# MCU.net
KiCad netlist of a schematic drawn in Altium Designer
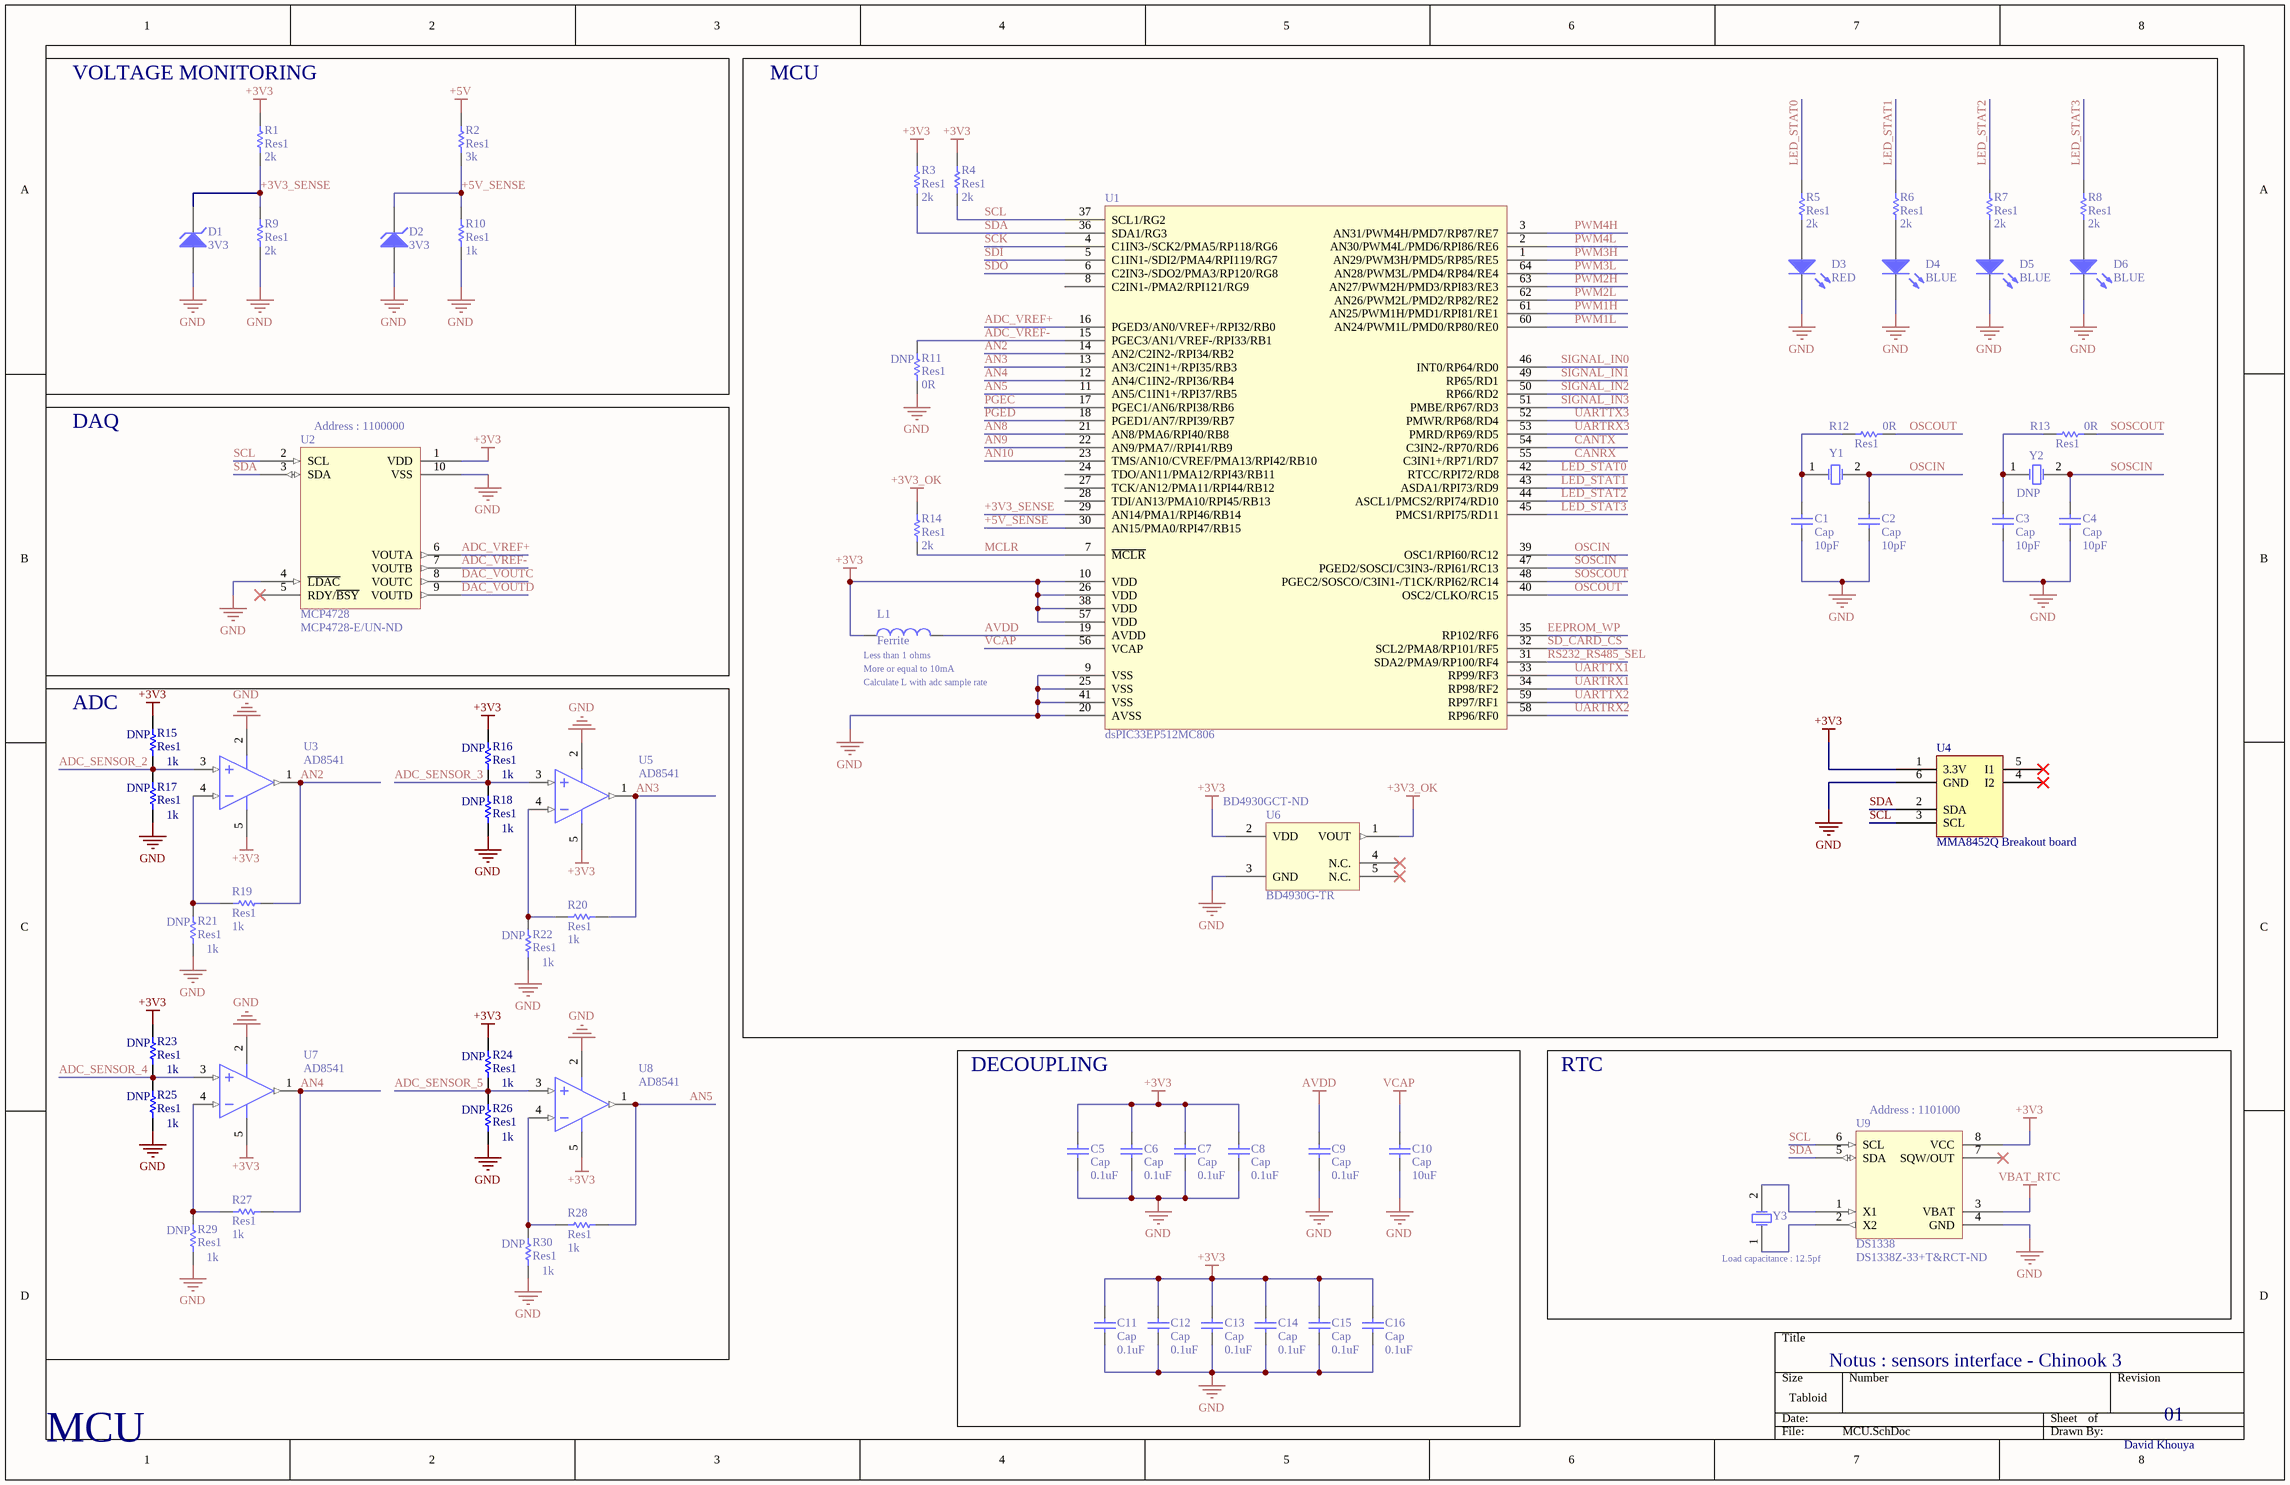
[diagram p0: MCU.SchDoc]

(export (version "E")
  (design (tool "Eeschema 10.0.6"))
  (components
    (comp (ref "C1")
      (value "Cap")
      (footprint "RESC2012N")
      (description "Capacitor")
      (fields (field (name "ALTIUM_VALUE") "10pF") (field (name "PUBLISHER") "Altium Limited"))
      (libsource (lib "Miscellaneous Devices") (part "Cap"))
    )
    (comp (ref "C2")
      (value "Cap")
      (footprint "RESC2012N")
      (description "Capacitor")
      (fields (field (name "ALTIUM_VALUE") "10pF") (field (name "PUBLISHER") "Altium Limited"))
      (libsource (lib "Miscellaneous Devices") (part "Cap"))
    )
    (comp (ref "C3")
      (value "Cap")
      (footprint "RESC2012N")
      (description "Capacitor")
      (fields (field (name "ALTIUM_VALUE") "10pF") (field (name "PUBLISHER") "Altium Limited"))
      (libsource (lib "Miscellaneous Devices") (part "Cap"))
    )
    (comp (ref "C4")
      (value "Cap")
      (footprint "RESC2012N")
      (description "Capacitor")
      (fields (field (name "ALTIUM_VALUE") "10pF") (field (name "PUBLISHER") "Altium Limited"))
      (libsource (lib "Miscellaneous Devices") (part "Cap"))
    )
    (comp (ref "C5")
      (value "Cap")
      (footprint "RESC2012N")
      (description "Capacitor")
      (fields (field (name "ALTIUM_VALUE") "0.1uF") (field (name "PUBLISHER") "Altium Limited"))
      (libsource (lib "Miscellaneous Devices") (part "Cap"))
    )
    (comp (ref "C6")
      (value "Cap")
      (footprint "RESC2012N")
      (description "Capacitor")
      (fields (field (name "ALTIUM_VALUE") "0.1uF") (field (name "PUBLISHER") "Altium Limited"))
      (libsource (lib "Miscellaneous Devices") (part "Cap"))
    )
    (comp (ref "C7")
      (value "Cap")
      (footprint "RESC2012N")
      (description "Capacitor")
      (fields (field (name "ALTIUM_VALUE") "0.1uF") (field (name "PUBLISHER") "Altium Limited"))
      (libsource (lib "Miscellaneous Devices") (part "Cap"))
    )
    (comp (ref "C8")
      (value "Cap")
      (footprint "RESC2012N")
      (description "Capacitor")
      (fields (field (name "ALTIUM_VALUE") "0.1uF") (field (name "PUBLISHER") "Altium Limited"))
      (libsource (lib "Miscellaneous Devices") (part "Cap"))
    )
    (comp (ref "C9")
      (value "Cap")
      (footprint "RESC2012N")
      (description "Capacitor")
      (fields (field (name "ALTIUM_VALUE") "0.1uF") (field (name "PUBLISHER") "Altium Limited"))
      (libsource (lib "Miscellaneous Devices") (part "Cap"))
    )
    (comp (ref "C10")
      (value "Cap")
      (footprint "RESC2012N")
      (description "Capacitor")
      (fields (field (name "ALTIUM_VALUE") "10uF") (field (name "PUBLISHER") "Altium Limited"))
      (libsource (lib "Miscellaneous Devices") (part "Cap"))
    )
    (comp (ref "C11")
      (value "Cap")
      (footprint "RESC2012N")
      (description "Capacitor")
      (fields (field (name "ALTIUM_VALUE") "0.1uF") (field (name "PUBLISHER") "Altium Limited"))
      (libsource (lib "Miscellaneous Devices") (part "Cap"))
    )
    (comp (ref "C12")
      (value "Cap")
      (footprint "RESC2012N")
      (description "Capacitor")
      (fields (field (name "ALTIUM_VALUE") "0.1uF") (field (name "PUBLISHER") "Altium Limited"))
      (libsource (lib "Miscellaneous Devices") (part "Cap"))
    )
    (comp (ref "C13")
      (value "Cap")
      (footprint "RESC2012N")
      (description "Capacitor")
      (fields (field (name "ALTIUM_VALUE") "0.1uF") (field (name "PUBLISHER") "Altium Limited"))
      (libsource (lib "Miscellaneous Devices") (part "Cap"))
    )
    (comp (ref "C14")
      (value "Cap")
      (footprint "RESC2012N")
      (description "Capacitor")
      (fields (field (name "ALTIUM_VALUE") "0.1uF") (field (name "PUBLISHER") "Altium Limited"))
      (libsource (lib "Miscellaneous Devices") (part "Cap"))
    )
    (comp (ref "C15")
      (value "Cap")
      (footprint "RESC2012N")
      (description "Capacitor")
      (fields (field (name "ALTIUM_VALUE") "0.1uF") (field (name "PUBLISHER") "Altium Limited"))
      (libsource (lib "Miscellaneous Devices") (part "Cap"))
    )
    (comp (ref "C16")
      (value "Cap")
      (footprint "RESC2012N")
      (description "Capacitor")
      (fields (field (name "ALTIUM_VALUE") "0.1uF") (field (name "PUBLISHER") "Altium Limited"))
      (libsource (lib "Miscellaneous Devices") (part "Cap"))
    )
    (comp (ref "D1")
      (value "3V3")
      (footprint "SOT23-3M")
      (description "Zener Diode")
      (fields (field (name "PUBLISHER") "Altium Limited"))
      (libsource (lib "Miscellaneous Devices") (part "D Zener"))
    )
    (comp (ref "D2")
      (value "3V3")
      (footprint "SOT23-3M")
      (description "Zener Diode")
      (fields (field (name "PUBLISHER") "Altium Limited"))
      (libsource (lib "Miscellaneous Devices") (part "D Zener"))
    )
    (comp (ref "D3")
      (value "RED")
      (footprint "0805_Diode")
      (description "Typical INFRARED GaAs LED")
      (fields (field (name "PUBLISHER") "Altium Limited"))
      (libsource (lib "Miscellaneous Devices") (part "LED0"))
    )
    (comp (ref "D4")
      (value "BLUE")
      (footprint "0805_Diode")
      (description "Typical INFRARED GaAs LED")
      (fields (field (name "PUBLISHER") "Altium Limited"))
      (libsource (lib "Miscellaneous Devices") (part "LED0"))
    )
    (comp (ref "D5")
      (value "BLUE")
      (footprint "0805_Diode")
      (description "Typical INFRARED GaAs LED")
      (fields (field (name "PUBLISHER") "Altium Limited"))
      (libsource (lib "Miscellaneous Devices") (part "LED0"))
    )
    (comp (ref "D6")
      (value "BLUE")
      (footprint "0805_Diode")
      (description "Typical INFRARED GaAs LED")
      (fields (field (name "PUBLISHER") "Altium Limited"))
      (libsource (lib "Miscellaneous Devices") (part "LED0"))
    )
    (comp (ref "L1")
      (value "Ferrite")
      (footprint "RESC2012N")
      (description "Inductor")
      (fields (field (name "PUBLISHER") "Altium Limited"))
      (libsource (lib "Miscellaneous Devices") (part "Inductor"))
    )
    (comp (ref "R1")
      (value "Res1")
      (footprint "RESC2012N")
      (description "Resistor")
      (fields (field (name "ALTIUM_VALUE") "2k") (field (name "PUBLISHER") "Altium Limited"))
      (libsource (lib "Miscellaneous Devices") (part "Res1"))
    )
    (comp (ref "R2")
      (value "Res1")
      (footprint "RESC2012N")
      (description "Resistor")
      (fields (field (name "ALTIUM_VALUE") "3k") (field (name "PUBLISHER") "Altium Limited"))
      (libsource (lib "Miscellaneous Devices") (part "Res1"))
    )
    (comp (ref "R3")
      (value "Res1")
      (footprint "RESC2012N")
      (description "Resistor")
      (fields (field (name "ALTIUM_VALUE") "2k") (field (name "PUBLISHER") "Altium Limited"))
      (libsource (lib "Miscellaneous Devices") (part "Res1"))
    )
    (comp (ref "R4")
      (value "Res1")
      (footprint "RESC2012N")
      (description "Resistor")
      (fields (field (name "ALTIUM_VALUE") "2k") (field (name "PUBLISHER") "Altium Limited"))
      (libsource (lib "Miscellaneous Devices") (part "Res1"))
    )
    (comp (ref "R5")
      (value "Res1")
      (footprint "RESC2012N")
      (description "Resistor")
      (fields (field (name "ALTIUM_VALUE") "2k") (field (name "PUBLISHER") "Altium Limited"))
      (libsource (lib "Miscellaneous Devices") (part "Res1"))
    )
    (comp (ref "R6")
      (value "Res1")
      (footprint "RESC2012N")
      (description "Resistor")
      (fields (field (name "ALTIUM_VALUE") "2k") (field (name "PUBLISHER") "Altium Limited"))
      (libsource (lib "Miscellaneous Devices") (part "Res1"))
    )
    (comp (ref "R7")
      (value "Res1")
      (footprint "RESC2012N")
      (description "Resistor")
      (fields (field (name "ALTIUM_VALUE") "2k") (field (name "PUBLISHER") "Altium Limited"))
      (libsource (lib "Miscellaneous Devices") (part "Res1"))
    )
    (comp (ref "R8")
      (value "Res1")
      (footprint "RESC2012N")
      (description "Resistor")
      (fields (field (name "ALTIUM_VALUE") "2k") (field (name "PUBLISHER") "Altium Limited"))
      (libsource (lib "Miscellaneous Devices") (part "Res1"))
    )
    (comp (ref "R9")
      (value "Res1")
      (footprint "RESC2012N")
      (description "Resistor")
      (fields (field (name "ALTIUM_VALUE") "2k") (field (name "PUBLISHER") "Altium Limited"))
      (libsource (lib "Miscellaneous Devices") (part "Res1"))
    )
    (comp (ref "R10")
      (value "Res1")
      (footprint "RESC2012N")
      (description "Resistor")
      (fields (field (name "ALTIUM_VALUE") "1k") (field (name "PUBLISHER") "Altium Limited"))
      (libsource (lib "Miscellaneous Devices") (part "Res1"))
    )
    (comp (ref "R11")
      (value "Res1")
      (footprint "RESC2012N")
      (description "Resistor")
      (fields
        (field (name "ALTIUM_VALUE") "0R")
        (field (name "DNP") "DNP")
        (field (name "PUBLISHER") "Altium Limited")
      )
      (libsource (lib "Miscellaneous Devices") (part "Res1"))
    )
    (comp (ref "R12")
      (value "Res1")
      (footprint "RESC2012N")
      (description "Resistor")
      (fields (field (name "ALTIUM_VALUE") "0R") (field (name "PUBLISHER") "Altium Limited"))
      (libsource (lib "Miscellaneous Devices") (part "Res1"))
    )
    (comp (ref "R13")
      (value "Res1")
      (footprint "RESC2012N")
      (description "Resistor")
      (fields (field (name "ALTIUM_VALUE") "0R") (field (name "PUBLISHER") "Altium Limited"))
      (libsource (lib "Miscellaneous Devices") (part "Res1"))
    )
    (comp (ref "R14")
      (value "Res1")
      (footprint "RESC2012N")
      (description "Resistor")
      (fields (field (name "ALTIUM_VALUE") "2k") (field (name "PUBLISHER") "Altium Limited"))
      (libsource (lib "Miscellaneous Devices") (part "Res1"))
    )
    (comp (ref "R15")
      (value "Res1")
      (footprint "RESC2012N")
      (description "Resistor")
      (fields
        (field (name "ALTIUM_VALUE") "1k")
        (field (name "DNP") "DNP")
        (field (name "PUBLISHER") "Altium Limited")
      )
      (libsource (lib "Miscellaneous Devices") (part "Res1"))
    )
    (comp (ref "R16")
      (value "Res1")
      (footprint "RESC2012N")
      (description "Resistor")
      (fields
        (field (name "ALTIUM_VALUE") "1k")
        (field (name "DNP") "DNP")
        (field (name "PUBLISHER") "Altium Limited")
      )
      (libsource (lib "Miscellaneous Devices") (part "Res1"))
    )
    (comp (ref "R17")
      (value "Res1")
      (footprint "RESC2012N")
      (description "Resistor")
      (fields
        (field (name "ALTIUM_VALUE") "1k")
        (field (name "DNP") "DNP")
        (field (name "PUBLISHER") "Altium Limited")
      )
      (libsource (lib "Miscellaneous Devices") (part "Res1"))
    )
    (comp (ref "R18")
      (value "Res1")
      (footprint "RESC2012N")
      (description "Resistor")
      (fields
        (field (name "ALTIUM_VALUE") "1k")
        (field (name "DNP") "DNP")
        (field (name "PUBLISHER") "Altium Limited")
      )
      (libsource (lib "Miscellaneous Devices") (part "Res1"))
    )
    (comp (ref "R19")
      (value "Res1")
      (footprint "RESC2012N")
      (description "Resistor")
      (fields (field (name "ALTIUM_VALUE") "1k") (field (name "PUBLISHER") "Altium Limited"))
      (libsource (lib "Miscellaneous Devices") (part "Res1"))
    )
    (comp (ref "R20")
      (value "Res1")
      (footprint "RESC2012N")
      (description "Resistor")
      (fields (field (name "ALTIUM_VALUE") "1k") (field (name "PUBLISHER") "Altium Limited"))
      (libsource (lib "Miscellaneous Devices") (part "Res1"))
    )
    (comp (ref "R21")
      (value "Res1")
      (footprint "RESC2012N")
      (description "Resistor")
      (fields
        (field (name "ALTIUM_VALUE") "1k")
        (field (name "DNP") "DNP")
        (field (name "PUBLISHER") "Altium Limited")
      )
      (libsource (lib "Miscellaneous Devices") (part "Res1"))
    )
    (comp (ref "R22")
      (value "Res1")
      (footprint "RESC2012N")
      (description "Resistor")
      (fields
        (field (name "ALTIUM_VALUE") "1k")
        (field (name "DNP") "DNP")
        (field (name "PUBLISHER") "Altium Limited")
      )
      (libsource (lib "Miscellaneous Devices") (part "Res1"))
    )
    (comp (ref "R23")
      (value "Res1")
      (footprint "RESC2012N")
      (description "Resistor")
      (fields
        (field (name "ALTIUM_VALUE") "1k")
        (field (name "DNP") "DNP")
        (field (name "PUBLISHER") "Altium Limited")
      )
      (libsource (lib "Miscellaneous Devices") (part "Res1"))
    )
    (comp (ref "R24")
      (value "Res1")
      (footprint "RESC2012N")
      (description "Resistor")
      (fields
        (field (name "ALTIUM_VALUE") "1k")
        (field (name "DNP") "DNP")
        (field (name "PUBLISHER") "Altium Limited")
      )
      (libsource (lib "Miscellaneous Devices") (part "Res1"))
    )
    (comp (ref "R25")
      (value "Res1")
      (footprint "RESC2012N")
      (description "Resistor")
      (fields
        (field (name "ALTIUM_VALUE") "1k")
        (field (name "DNP") "DNP")
        (field (name "PUBLISHER") "Altium Limited")
      )
      (libsource (lib "Miscellaneous Devices") (part "Res1"))
    )
    (comp (ref "R26")
      (value "Res1")
      (footprint "RESC2012N")
      (description "Resistor")
      (fields
        (field (name "ALTIUM_VALUE") "1k")
        (field (name "DNP") "DNP")
        (field (name "PUBLISHER") "Altium Limited")
      )
      (libsource (lib "Miscellaneous Devices") (part "Res1"))
    )
    (comp (ref "R27")
      (value "Res1")
      (footprint "RESC2012N")
      (description "Resistor")
      (fields (field (name "ALTIUM_VALUE") "1k") (field (name "PUBLISHER") "Altium Limited"))
      (libsource (lib "Miscellaneous Devices") (part "Res1"))
    )
    (comp (ref "R28")
      (value "Res1")
      (footprint "RESC2012N")
      (description "Resistor")
      (fields (field (name "ALTIUM_VALUE") "1k") (field (name "PUBLISHER") "Altium Limited"))
      (libsource (lib "Miscellaneous Devices") (part "Res1"))
    )
    (comp (ref "R29")
      (value "Res1")
      (footprint "RESC2012N")
      (description "Resistor")
      (fields
        (field (name "ALTIUM_VALUE") "1k")
        (field (name "DNP") "DNP")
        (field (name "PUBLISHER") "Altium Limited")
      )
      (libsource (lib "Miscellaneous Devices") (part "Res1"))
    )
    (comp (ref "R30")
      (value "Res1")
      (footprint "RESC2012N")
      (description "Resistor")
      (fields
        (field (name "ALTIUM_VALUE") "1k")
        (field (name "DNP") "DNP")
        (field (name "PUBLISHER") "Altium Limited")
      )
      (libsource (lib "Miscellaneous Devices") (part "Res1"))
    )
    (comp (ref "U1")
      (value "dsPIC33EP512MC806")
      (footprint "TQFP-PT64_M")
      (description "16 bits microcontroller with Digital signal controller")
      (libsource (lib "dkhouya") (part "dsPIC33EP512MC806"))
    )
    (comp (ref "U2")
      (value "MCP4728")
      (description "12-Bit, Quad Digital-to-Analog Converter with EEPROM Memory")
      (fields (field (name "SUPPLIER PART NUMBER 1") "MCP4728-E/UN-ND"))
      (libsource (lib "dkhouya") (part "MCP4728"))
    )
    (comp (ref "U3")
      (value "AD8541")
      (footprint "RT-5")
      (description "CMOS Rail-to-Rail General-Purpose Amplifiers")
      (libsource (lib "dkhouya") (part "AD8541"))
    )
    (comp (ref "U4")
      (value "MMA8452Q Breakout board")
      (footprint "MMA8452Q Breakout board")
      (description "Triple axis accelerometer breakout board")
      (libsource (lib "dkhouya") (part "MMA8452Q Breakout board"))
    )
    (comp (ref "U5")
      (value "AD8541")
      (footprint "RT-5")
      (description "CMOS Rail-to-Rail General-Purpose Amplifiers")
      (libsource (lib "dkhouya") (part "AD8541"))
    )
    (comp (ref "U6")
      (value "BD4930G-TR")
      (footprint "SSOP5")
      (description "5V Voltage supervisor")
      (fields (field (name "SUPPLIER PART NUMBER 1") "BD4930GCT-ND"))
      (libsource (lib "dkhouya") (part "BD4950G-TR"))
    )
    (comp (ref "U7")
      (value "AD8541")
      (footprint "RT-5")
      (description "CMOS Rail-to-Rail General-Purpose Amplifiers")
      (libsource (lib "dkhouya") (part "AD8541"))
    )
    (comp (ref "U8")
      (value "AD8541")
      (footprint "RT-5")
      (description "CMOS Rail-to-Rail General-Purpose Amplifiers")
      (libsource (lib "dkhouya") (part "AD8541"))
    )
    (comp (ref "U9")
      (value "DS1338")
      (footprint "8SOIC-1")
      (description "I2C RTC with 56-Byte NV RAM")
      (fields (field (name "SUPPLIER PART NUMBER 1") "DS1338Z-33+T&RCT-ND"))
      (libsource (lib "dkhouya") (part "DS1338"))
    )
    (comp (ref "Y1")
      (value "~")
      (footprint "HC49/4H_SMX")
      (description "Crystal Oscillator")
      (fields (field (name "PUBLISHER") "Altium Limited"))
      (libsource (lib "Miscellaneous Devices") (part "XTAL"))
    )
    (comp (ref "Y2")
      (value "~")
      (footprint "HC49/4H_SMX")
      (description "Crystal Oscillator")
      (fields (field (name "DNP") "DNP") (field (name "PUBLISHER") "Altium Limited"))
      (libsource (lib "Miscellaneous Devices") (part "XTAL"))
    )
    (comp (ref "Y3")
      (value "~")
      (footprint "crystalcustom")
      (description "Crystal Oscillator")
      (fields (field (name "PUBLISHER") "Altium Limited"))
      (libsource (lib "Miscellaneous Devices") (part "XTAL"))
    )
  )
  (nets
    (net (code "1") (name "+3V3") (class "Default")
      (node (ref "C11") (pin "2") (pinfunction "2_2") (pintype "passive"))
      (node (ref "C12") (pin "2") (pinfunction "2_2") (pintype "passive"))
      (node (ref "C13") (pin "2") (pinfunction "2_2") (pintype "passive"))
      (node (ref "C14") (pin "2") (pinfunction "2_2") (pintype "passive"))
      (node (ref "C15") (pin "2") (pinfunction "2_2") (pintype "passive"))
      (node (ref "C16") (pin "2") (pinfunction "2_2") (pintype "passive"))
      (node (ref "C5") (pin "2") (pinfunction "2_2") (pintype "passive"))
      (node (ref "C6") (pin "2") (pinfunction "2_2") (pintype "passive"))
      (node (ref "C7") (pin "2") (pinfunction "2_2") (pintype "passive"))
      (node (ref "C8") (pin "2") (pinfunction "2_2") (pintype "passive"))
      (node (ref "L1") (pin "1") (pinfunction "1_1") (pintype "passive"))
      (node (ref "R1") (pin "1") (pinfunction "1_1") (pintype "passive"))
      (node (ref "R15") (pin "1") (pinfunction "1_1") (pintype "passive"))
      (node (ref "R16") (pin "1") (pinfunction "1_1") (pintype "passive"))
      (node (ref "R23") (pin "1") (pinfunction "1_1") (pintype "passive"))
      (node (ref "R24") (pin "1") (pinfunction "1_1") (pintype "passive"))
      (node (ref "R3") (pin "1") (pinfunction "1_1") (pintype "passive"))
      (node (ref "R4") (pin "1") (pinfunction "1_1") (pintype "passive"))
      (node (ref "U1") (pin "10") (pinfunction "VDD_10") (pintype "passive"))
      (node (ref "U1") (pin "26") (pinfunction "VDD_26") (pintype "passive"))
      (node (ref "U1") (pin "38") (pinfunction "VDD_38") (pintype "passive"))
      (node (ref "U1") (pin "57") (pinfunction "VDD_57") (pintype "passive"))
      (node (ref "U2") (pin "1") (pinfunction "VDD_1") (pintype "power_in"))
      (node (ref "U3") (pin "5") (pinfunction "V+_5") (pintype "power_in"))
      (node (ref "U4") (pin "1") (pinfunction "3.3V_1") (pintype "passive"))
      (node (ref "U5") (pin "5") (pinfunction "V+_5") (pintype "power_in"))
      (node (ref "U6") (pin "2") (pinfunction "VDD_2") (pintype "power_in"))
      (node (ref "U7") (pin "5") (pinfunction "V+_5") (pintype "power_in"))
      (node (ref "U8") (pin "5") (pinfunction "V+_5") (pintype "power_in"))
      (node (ref "U9") (pin "8") (pinfunction "VCC_8") (pintype "power_in"))
    )
    (net (code "2") (name "+3V3_OK") (class "Default")
      (node (ref "R14") (pin "1") (pinfunction "1_1") (pintype "passive"))
      (node (ref "U6") (pin "1") (pinfunction "VOUT_1") (pintype "output"))
    )
    (net (code "3") (name "+5V") (class "Default")
      (node (ref "R2") (pin "1") (pinfunction "1_1") (pintype "passive"))
    )
    (net (code "4") (name "/+3V3_SENSE") (class "Default")
      (node (ref "D1") (pin "2") (pinfunction "K_2") (pintype "passive"))
      (node (ref "R1") (pin "2") (pinfunction "2_2") (pintype "passive"))
      (node (ref "R9") (pin "1") (pinfunction "1_1") (pintype "passive"))
      (node (ref "U1") (pin "29") (pinfunction "AN14/PMA1/RPI46/RB14_29") (pintype "passive"))
    )
    (net (code "5") (name "/+5V_SENSE") (class "Default")
      (node (ref "D2") (pin "2") (pinfunction "K_2") (pintype "passive"))
      (node (ref "R10") (pin "1") (pinfunction "1_1") (pintype "passive"))
      (node (ref "R2") (pin "2") (pinfunction "2_2") (pintype "passive"))
      (node (ref "U1") (pin "30") (pinfunction "AN15/PMA0/RPI47/RB15_30") (pintype "passive"))
    )
    (net (code "6") (name "/ADC_SENSOR_2") (class "Default")
      (node (ref "R15") (pin "2") (pinfunction "2_2") (pintype "passive"))
      (node (ref "R17") (pin "1") (pinfunction "1_1") (pintype "passive"))
      (node (ref "U3") (pin "3") (pinfunction "IN+_A_3") (pintype "input"))
    )
    (net (code "7") (name "/ADC_SENSOR_3") (class "Default")
      (node (ref "R16") (pin "2") (pinfunction "2_2") (pintype "passive"))
      (node (ref "R18") (pin "1") (pinfunction "1_1") (pintype "passive"))
      (node (ref "U5") (pin "3") (pinfunction "IN+_A_3") (pintype "input"))
    )
    (net (code "8") (name "/ADC_SENSOR_4") (class "Default")
      (node (ref "R23") (pin "2") (pinfunction "2_2") (pintype "passive"))
      (node (ref "R25") (pin "1") (pinfunction "1_1") (pintype "passive"))
      (node (ref "U7") (pin "3") (pinfunction "IN+_A_3") (pintype "input"))
    )
    (net (code "9") (name "/ADC_SENSOR_5") (class "Default")
      (node (ref "R24") (pin "2") (pinfunction "2_2") (pintype "passive"))
      (node (ref "R26") (pin "1") (pinfunction "1_1") (pintype "passive"))
      (node (ref "U8") (pin "3") (pinfunction "IN+_A_3") (pintype "input"))
    )
    (net (code "10") (name "/ADC_VREF+") (class "Default")
      (node (ref "U1") (pin "16") (pinfunction "PGED3/AN0/VREF+/RPI32/RB0_16") (pintype "passive"))
      (node (ref "U2") (pin "6") (pinfunction "VOUTA_6") (pintype "output"))
    )
    (net (code "11") (name "/ADC_VREF-") (class "Default")
      (node (ref "R11") (pin "1") (pinfunction "1_1") (pintype "passive"))
      (node (ref "U1") (pin "15") (pinfunction "PGEC3/AN1/VREF-/RPI33/RB1_15") (pintype "passive"))
      (node (ref "U2") (pin "7") (pinfunction "VOUTB_7") (pintype "output"))
    )
    (net (code "12") (name "/AN2") (class "Default")
      (node (ref "R19") (pin "2") (pinfunction "2_2") (pintype "passive"))
      (node (ref "U1") (pin "14") (pinfunction "AN2/C2IN2-/RPI34/RB2_14") (pintype "passive"))
      (node (ref "U3") (pin "1") (pinfunction "OUT_A_1") (pintype "output"))
    )
    (net (code "13") (name "/AN3") (class "Default")
      (node (ref "R20") (pin "2") (pinfunction "2_2") (pintype "passive"))
      (node (ref "U1") (pin "13") (pinfunction "AN3/C2IN1+/RPI35/RB3_13") (pintype "passive"))
      (node (ref "U5") (pin "1") (pinfunction "OUT_A_1") (pintype "output"))
    )
    (net (code "14") (name "/AN4") (class "Default")
      (node (ref "R27") (pin "2") (pinfunction "2_2") (pintype "passive"))
      (node (ref "U1") (pin "12") (pinfunction "AN4/C1IN2-/RPI36/RB4_12") (pintype "passive"))
      (node (ref "U7") (pin "1") (pinfunction "OUT_A_1") (pintype "output"))
    )
    (net (code "15") (name "/AN5") (class "Default")
      (node (ref "R28") (pin "2") (pinfunction "2_2") (pintype "passive"))
      (node (ref "U1") (pin "11") (pinfunction "AN5/C1IN1+/RPI37/RB5_11") (pintype "passive"))
      (node (ref "U8") (pin "1") (pinfunction "OUT_A_1") (pintype "output"))
    )
    (net (code "16") (name "/AN8") (class "Default")
      (node (ref "U1") (pin "21") (pinfunction "AN8/PMA6/RPI40/RB8_21") (pintype "passive"))
    )
    (net (code "17") (name "/AN9") (class "Default")
      (node (ref "U1") (pin "22") (pinfunction "AN9/PMA7//RPI41/RB9_22") (pintype "passive"))
    )
    (net (code "18") (name "/AN10") (class "Default")
      (node (ref "U1") (pin "23") (pinfunction "TMS/AN10/CVREF/PMA13/RPI42/RB10_23") (pintype "passive"))
    )
    (net (code "19") (name "/CANRX") (class "Default")
      (node (ref "U1") (pin "55") (pinfunction "C3IN1+/RP71/RD7_55") (pintype "passive"))
    )
    (net (code "20") (name "/CANTX") (class "Default")
      (node (ref "U1") (pin "54") (pinfunction "C3IN2-/RP70/RD6_54") (pintype "passive"))
    )
    (net (code "21") (name "/DAC_VOUTC") (class "Default")
      (node (ref "U2") (pin "8") (pinfunction "VOUTC_8") (pintype "output"))
    )
    (net (code "22") (name "/DAC_VOUTD") (class "Default")
      (node (ref "U2") (pin "9") (pinfunction "VOUTD_9") (pintype "output"))
    )
    (net (code "23") (name "/EEPROM_WP") (class "Default")
      (node (ref "U1") (pin "35") (pinfunction "RP102/RF6_35") (pintype "passive"))
    )
    (net (code "24") (name "/LED_STAT0") (class "Default")
      (node (ref "R5") (pin "1") (pinfunction "1_1") (pintype "passive"))
      (node (ref "U1") (pin "42") (pinfunction "RTCC/RPI72/RD8_42") (pintype "passive"))
    )
    (net (code "25") (name "/LED_STAT1") (class "Default")
      (node (ref "R6") (pin "1") (pinfunction "1_1") (pintype "passive"))
      (node (ref "U1") (pin "43") (pinfunction "ASDA1/RPI73/RD9_43") (pintype "passive"))
    )
    (net (code "26") (name "/LED_STAT2") (class "Default")
      (node (ref "R7") (pin "1") (pinfunction "1_1") (pintype "passive"))
      (node (ref "U1") (pin "44") (pinfunction "ASCL1/PMCS2/RPI74/RD10_44") (pintype "passive"))
    )
    (net (code "27") (name "/LED_STAT3") (class "Default")
      (node (ref "R8") (pin "1") (pinfunction "1_1") (pintype "passive"))
      (node (ref "U1") (pin "45") (pinfunction "PMCS1/RPI75/RD11_45") (pintype "passive"))
    )
    (net (code "28") (name "/MCLR") (class "Default")
      (node (ref "R14") (pin "2") (pinfunction "2_2") (pintype "passive"))
      (node (ref "U1") (pin "7") (pinfunction "~{MCLR}_7") (pintype "passive"))
    )
    (net (code "29") (name "/OSCIN") (class "Default")
      (node (ref "C2") (pin "2") (pinfunction "2_2") (pintype "passive"))
      (node (ref "U1") (pin "39") (pinfunction "OSC1/RPI60/RC12_39") (pintype "passive"))
      (node (ref "Y1") (pin "2") (pinfunction "OSC2_2") (pintype "passive"))
    )
    (net (code "30") (name "/OSCOUT") (class "Default")
      (node (ref "R12") (pin "1") (pinfunction "1_1") (pintype "passive"))
      (node (ref "U1") (pin "40") (pinfunction "OSC2/CLKO/RC15_40") (pintype "passive"))
    )
    (net (code "31") (name "/PGEC") (class "Default")
      (node (ref "U1") (pin "17") (pinfunction "PGEC1/AN6/RPI38/RB6_17") (pintype "passive"))
    )
    (net (code "32") (name "/PGED") (class "Default")
      (node (ref "U1") (pin "18") (pinfunction "PGED1/AN7/RPI39/RB7_18") (pintype "passive"))
    )
    (net (code "33") (name "/PWM1H") (class "Default")
      (node (ref "U1") (pin "61") (pinfunction "AN25/PWM1H/PMD1/RPI81/RE1_61") (pintype "passive"))
    )
    (net (code "34") (name "/PWM1L") (class "Default")
      (node (ref "U1") (pin "60") (pinfunction "AN24/PWM1L/PMD0/RP80/RE0_60") (pintype "passive"))
    )
    (net (code "35") (name "/PWM2H") (class "Default")
      (node (ref "U1") (pin "63") (pinfunction "AN27/PWM2H/PMD3/RPI83/RE3_63") (pintype "passive"))
    )
    (net (code "36") (name "/PWM2L") (class "Default")
      (node (ref "U1") (pin "62") (pinfunction "AN26/PWM2L/PMD2/RP82/RE2_62") (pintype "passive"))
    )
    (net (code "37") (name "/PWM3H") (class "Default")
      (node (ref "U1") (pin "1") (pinfunction "AN29/PWM3H/PMD5/RP85/RE5_1") (pintype "passive"))
    )
    (net (code "38") (name "/PWM3L") (class "Default")
      (node (ref "U1") (pin "64") (pinfunction "AN28/PWM3L/PMD4/RP84/RE4_64") (pintype "passive"))
    )
    (net (code "39") (name "/PWM4H") (class "Default")
      (node (ref "U1") (pin "3") (pinfunction "AN31/PWM4H/PMD7/RP87/RE7_3") (pintype "passive"))
    )
    (net (code "40") (name "/PWM4L") (class "Default")
      (node (ref "U1") (pin "2") (pinfunction "AN30/PWM4L/PMD6/RPI86/RE6_2") (pintype "passive"))
    )
    (net (code "41") (name "/RS232_RS485_SEL") (class "Default")
      (node (ref "U1") (pin "31") (pinfunction "SDA2/PMA9/RP100/RF4_31") (pintype "passive"))
    )
    (net (code "42") (name "/SCK") (class "Default")
      (node (ref "U1") (pin "4") (pinfunction "C1IN3-/SCK2/PMA5/RP118/RG6_4") (pintype "passive"))
    )
    (net (code "43") (name "/SCL") (class "Default")
      (node (ref "R4") (pin "2") (pinfunction "2_2") (pintype "passive"))
      (node (ref "U1") (pin "37") (pinfunction "SCL1/RG2_37") (pintype "passive"))
      (node (ref "U2") (pin "2") (pinfunction "SCL_2") (pintype "input"))
      (node (ref "U4") (pin "3") (pinfunction "SCL_3") (pintype "passive"))
      (node (ref "U9") (pin "6") (pinfunction "SCL_6") (pintype "input"))
    )
    (net (code "44") (name "/SDA") (class "Default")
      (node (ref "R3") (pin "2") (pinfunction "2_2") (pintype "passive"))
      (node (ref "U1") (pin "36") (pinfunction "SDA1/RG3_36") (pintype "passive"))
      (node (ref "U2") (pin "3") (pinfunction "SDA_3") (pintype "bidirectional"))
      (node (ref "U4") (pin "2") (pinfunction "SDA_2") (pintype "passive"))
      (node (ref "U9") (pin "5") (pinfunction "SDA_5") (pintype "bidirectional"))
    )
    (net (code "45") (name "/SDI") (class "Default")
      (node (ref "U1") (pin "5") (pinfunction "C1IN1-/SDI2/PMA4/RPI119/RG7_5") (pintype "passive"))
    )
    (net (code "46") (name "/SDO") (class "Default")
      (node (ref "U1") (pin "6") (pinfunction "C2IN3-/SDO2/PMA3/RP120/RG8_6") (pintype "passive"))
    )
    (net (code "47") (name "/SD_CARD_CS") (class "Default")
      (node (ref "U1") (pin "32") (pinfunction "SCL2/PMA8/RP101/RF5_32") (pintype "passive"))
    )
    (net (code "48") (name "/SIGNAL_IN0") (class "Default")
      (node (ref "U1") (pin "46") (pinfunction "INT0/RP64/RD0_46") (pintype "passive"))
    )
    (net (code "49") (name "/SIGNAL_IN1") (class "Default")
      (node (ref "U1") (pin "49") (pinfunction "RP65/RD1_49") (pintype "passive"))
    )
    (net (code "50") (name "/SIGNAL_IN2") (class "Default")
      (node (ref "U1") (pin "50") (pinfunction "RP66/RD2_50") (pintype "passive"))
    )
    (net (code "51") (name "/SIGNAL_IN3") (class "Default")
      (node (ref "U1") (pin "51") (pinfunction "PMBE/RP67/RD3_51") (pintype "passive"))
    )
    (net (code "52") (name "/SOSCIN") (class "Default")
      (node (ref "C4") (pin "2") (pinfunction "2_2") (pintype "passive"))
      (node (ref "U1") (pin "47") (pinfunction "PGED2/SOSCI/C3IN3-/RPI61/RC13_47") (pintype "passive"))
      (node (ref "Y2") (pin "2") (pinfunction "OSC2_2") (pintype "passive"))
    )
    (net (code "53") (name "/SOSCOUT") (class "Default")
      (node (ref "R13") (pin "1") (pinfunction "1_1") (pintype "passive"))
      (node (ref "U1") (pin "48") (pinfunction "PGEC2/SOSCO/C3IN1-/T1CK/RPI62/RC14_48") (pintype "passive"))
    )
    (net (code "54") (name "/UARTRX1") (class "Default")
      (node (ref "U1") (pin "34") (pinfunction "RP98/RF2_34") (pintype "passive"))
    )
    (net (code "55") (name "/UARTRX2") (class "Default")
      (node (ref "U1") (pin "58") (pinfunction "RP96/RF0_58") (pintype "passive"))
    )
    (net (code "56") (name "/UARTRX3") (class "Default")
      (node (ref "U1") (pin "53") (pinfunction "PMRD/RP69/RD5_53") (pintype "passive"))
    )
    (net (code "57") (name "/UARTTX1") (class "Default")
      (node (ref "U1") (pin "33") (pinfunction "RP99/RF3_33") (pintype "passive"))
    )
    (net (code "58") (name "/UARTTX2") (class "Default")
      (node (ref "U1") (pin "59") (pinfunction "RP97/RF1_59") (pintype "passive"))
    )
    (net (code "59") (name "/UARTTX3") (class "Default")
      (node (ref "U1") (pin "52") (pinfunction "PMWR/RP68/RD4_52") (pintype "passive"))
    )
    (net (code "60") (name "AVDD") (class "Default")
      (node (ref "C9") (pin "2") (pinfunction "2_2") (pintype "passive"))
      (node (ref "L1") (pin "2") (pinfunction "2_2") (pintype "passive"))
      (node (ref "U1") (pin "19") (pinfunction "AVDD_19") (pintype "passive"))
    )
    (net (code "61") (name "GND") (class "Default")
      (node (ref "C1") (pin "1") (pinfunction "1_1") (pintype "passive"))
      (node (ref "C10") (pin "1") (pinfunction "1_1") (pintype "passive"))
      (node (ref "C11") (pin "1") (pinfunction "1_1") (pintype "passive"))
      (node (ref "C12") (pin "1") (pinfunction "1_1") (pintype "passive"))
      (node (ref "C13") (pin "1") (pinfunction "1_1") (pintype "passive"))
      (node (ref "C14") (pin "1") (pinfunction "1_1") (pintype "passive"))
      (node (ref "C15") (pin "1") (pinfunction "1_1") (pintype "passive"))
      (node (ref "C16") (pin "1") (pinfunction "1_1") (pintype "passive"))
      (node (ref "C2") (pin "1") (pinfunction "1_1") (pintype "passive"))
      (node (ref "C3") (pin "1") (pinfunction "1_1") (pintype "passive"))
      (node (ref "C4") (pin "1") (pinfunction "1_1") (pintype "passive"))
      (node (ref "C5") (pin "1") (pinfunction "1_1") (pintype "passive"))
      (node (ref "C6") (pin "1") (pinfunction "1_1") (pintype "passive"))
      (node (ref "C7") (pin "1") (pinfunction "1_1") (pintype "passive"))
      (node (ref "C8") (pin "1") (pinfunction "1_1") (pintype "passive"))
      (node (ref "C9") (pin "1") (pinfunction "1_1") (pintype "passive"))
      (node (ref "D1") (pin "1") (pinfunction "A_1") (pintype "passive"))
      (node (ref "D2") (pin "1") (pinfunction "A_1") (pintype "passive"))
      (node (ref "D3") (pin "2") (pinfunction "K_2") (pintype "passive"))
      (node (ref "D4") (pin "2") (pinfunction "K_2") (pintype "passive"))
      (node (ref "D5") (pin "2") (pinfunction "K_2") (pintype "passive"))
      (node (ref "D6") (pin "2") (pinfunction "K_2") (pintype "passive"))
      (node (ref "R10") (pin "2") (pinfunction "2_2") (pintype "passive"))
      (node (ref "R11") (pin "2") (pinfunction "2_2") (pintype "passive"))
      (node (ref "R17") (pin "2") (pinfunction "2_2") (pintype "passive"))
      (node (ref "R18") (pin "2") (pinfunction "2_2") (pintype "passive"))
      (node (ref "R21") (pin "2") (pinfunction "2_2") (pintype "passive"))
      (node (ref "R22") (pin "2") (pinfunction "2_2") (pintype "passive"))
      (node (ref "R25") (pin "2") (pinfunction "2_2") (pintype "passive"))
      (node (ref "R26") (pin "2") (pinfunction "2_2") (pintype "passive"))
      (node (ref "R29") (pin "2") (pinfunction "2_2") (pintype "passive"))
      (node (ref "R30") (pin "2") (pinfunction "2_2") (pintype "passive"))
      (node (ref "R9") (pin "2") (pinfunction "2_2") (pintype "passive"))
      (node (ref "U1") (pin "20") (pinfunction "AVSS_20") (pintype "passive"))
      (node (ref "U1") (pin "25") (pinfunction "VSS_25") (pintype "passive"))
      (node (ref "U1") (pin "41") (pinfunction "VSS_41") (pintype "passive"))
      (node (ref "U1") (pin "9") (pinfunction "VSS_9") (pintype "passive"))
      (node (ref "U2") (pin "10") (pinfunction "VSS_10") (pintype "power_in"))
      (node (ref "U2") (pin "4") (pinfunction "~{LDAC}_4") (pintype "input"))
      (node (ref "U3") (pin "2") (pinfunction "V-_2") (pintype "power_in"))
      (node (ref "U4") (pin "6") (pinfunction "GND_6") (pintype "passive"))
      (node (ref "U5") (pin "2") (pinfunction "V-_2") (pintype "power_in"))
      (node (ref "U6") (pin "3") (pinfunction "GND_3") (pintype "passive"))
      (node (ref "U7") (pin "2") (pinfunction "V-_2") (pintype "power_in"))
      (node (ref "U8") (pin "2") (pinfunction "V-_2") (pintype "power_in"))
      (node (ref "U9") (pin "4") (pinfunction "GND_4") (pintype "power_in"))
    )
    (net (code "62") (name "Net-(D3-A)") (class "Default")
      (node (ref "D3") (pin "1") (pinfunction "A_1") (pintype "passive"))
      (node (ref "R5") (pin "2") (pinfunction "2_2") (pintype "passive"))
    )
    (net (code "63") (name "Net-(D4-A)") (class "Default")
      (node (ref "D4") (pin "1") (pinfunction "A_1") (pintype "passive"))
      (node (ref "R6") (pin "2") (pinfunction "2_2") (pintype "passive"))
    )
    (net (code "64") (name "Net-(D5-A)") (class "Default")
      (node (ref "D5") (pin "1") (pinfunction "A_1") (pintype "passive"))
      (node (ref "R7") (pin "2") (pinfunction "2_2") (pintype "passive"))
    )
    (net (code "65") (name "Net-(D6-A)") (class "Default")
      (node (ref "D6") (pin "1") (pinfunction "A_1") (pintype "passive"))
      (node (ref "R8") (pin "2") (pinfunction "2_2") (pintype "passive"))
    )
    (net (code "66") (name "Net-(U3-IN-_A)") (class "Default")
      (node (ref "R19") (pin "1") (pinfunction "1_1") (pintype "passive"))
      (node (ref "R21") (pin "1") (pinfunction "1_1") (pintype "passive"))
      (node (ref "U3") (pin "4") (pinfunction "IN-_A_4") (pintype "input"))
    )
    (net (code "67") (name "Net-(U5-IN-_A)") (class "Default")
      (node (ref "R20") (pin "1") (pinfunction "1_1") (pintype "passive"))
      (node (ref "R22") (pin "1") (pinfunction "1_1") (pintype "passive"))
      (node (ref "U5") (pin "4") (pinfunction "IN-_A_4") (pintype "input"))
    )
    (net (code "68") (name "Net-(U7-IN-_A)") (class "Default")
      (node (ref "R27") (pin "1") (pinfunction "1_1") (pintype "passive"))
      (node (ref "R29") (pin "1") (pinfunction "1_1") (pintype "passive"))
      (node (ref "U7") (pin "4") (pinfunction "IN-_A_4") (pintype "input"))
    )
    (net (code "69") (name "Net-(U8-IN-_A)") (class "Default")
      (node (ref "R28") (pin "1") (pinfunction "1_1") (pintype "passive"))
      (node (ref "R30") (pin "1") (pinfunction "1_1") (pintype "passive"))
      (node (ref "U8") (pin "4") (pinfunction "IN-_A_4") (pintype "input"))
    )
    (net (code "70") (name "Net-(U9-X1)") (class "Default")
      (node (ref "U9") (pin "1") (pinfunction "X1_1") (pintype "input"))
      (node (ref "Y3") (pin "2") (pinfunction "OSC2_2") (pintype "passive"))
    )
    (net (code "71") (name "Net-(U9-X2)") (class "Default")
      (node (ref "U9") (pin "2") (pinfunction "X2_2") (pintype "output"))
      (node (ref "Y3") (pin "1") (pinfunction "OSC1_1") (pintype "passive"))
    )
    (net (code "72") (name "Net-(Y1-OSC1)") (class "Default")
      (node (ref "C1") (pin "2") (pinfunction "2_2") (pintype "passive"))
      (node (ref "R12") (pin "2") (pinfunction "2_2") (pintype "passive"))
      (node (ref "Y1") (pin "1") (pinfunction "OSC1_1") (pintype "passive"))
    )
    (net (code "73") (name "Net-(Y2-OSC1)") (class "Default")
      (node (ref "C3") (pin "2") (pinfunction "2_2") (pintype "passive"))
      (node (ref "R13") (pin "2") (pinfunction "2_2") (pintype "passive"))
      (node (ref "Y2") (pin "1") (pinfunction "OSC1_1") (pintype "passive"))
    )
    (net (code "74") (name "VBAT_RTC") (class "Default")
      (node (ref "U9") (pin "3") (pinfunction "VBAT_3") (pintype "power_in"))
    )
    (net (code "75") (name "VCAP") (class "Default")
      (node (ref "C10") (pin "2") (pinfunction "2_2") (pintype "passive"))
      (node (ref "U1") (pin "56") (pinfunction "VCAP_56") (pintype "passive"))
    )
    (net (code "76") (name "unconnected-(U1-C2IN1-{slash}PMA2{slash}RPI121{slash}RG9-Pad8)") (class "Default")
      (node (ref "U1") (pin "8") (pinfunction "C2IN1-/PMA2/RPI121/RG9_8") (pintype "passive"))
    )
    (net (code "77") (name "unconnected-(U1-TCK{slash}AN12{slash}PMA11{slash}RPI44{slash}RB12-Pad27)") (class "Default")
      (node (ref "U1") (pin "27") (pinfunction "TCK/AN12/PMA11/RPI44/RB12_27") (pintype "passive"))
    )
    (net (code "78") (name "unconnected-(U1-TDI{slash}AN13{slash}PMA10{slash}RPI45{slash}RB13-Pad28)") (class "Default")
      (node (ref "U1") (pin "28") (pinfunction "TDI/AN13/PMA10/RPI45/RB13_28") (pintype "passive"))
    )
    (net (code "79") (name "unconnected-(U1-TDO{slash}AN11{slash}PMA12{slash}RPI43{slash}RB11-Pad24)") (class "Default")
      (node (ref "U1") (pin "24") (pinfunction "TDO/AN11/PMA12/RPI43/RB11_24") (pintype "passive"))
    )
    (net (code "80") (name "unconnected-(U2-RDY{slash}~{BSY}-Pad5)") (class "Default")
      (node (ref "U2") (pin "5") (pinfunction "RDY/~{BSY}_5") (pintype "open_collector+no_connect"))
    )
    (net (code "81") (name "unconnected-(U4-I1-Pad5)") (class "Default")
      (node (ref "U4") (pin "5") (pinfunction "I1_5") (pintype "passive+no_connect"))
    )
    (net (code "82") (name "unconnected-(U4-I2-Pad4)") (class "Default")
      (node (ref "U4") (pin "4") (pinfunction "I2_4") (pintype "passive+no_connect"))
    )
    (net (code "83") (name "unconnected-(U6-N.C.-Pad4)") (class "Default")
      (node (ref "U6") (pin "4") (pinfunction "N.C._4") (pintype "passive+no_connect"))
    )
    (net (code "84") (name "unconnected-(U6-N.C.-Pad5)") (class "Default")
      (node (ref "U6") (pin "5") (pinfunction "N.C._5") (pintype "passive+no_connect"))
    )
    (net (code "85") (name "unconnected-(U9-SQW{slash}OUT-Pad7)") (class "Default")
      (node (ref "U9") (pin "7") (pinfunction "SQW/OUT_7") (pintype "open_collector+no_connect"))
    )
  )
)
